# V1_0.net
KiCad netlist of a schematic drawn in Altium Designer
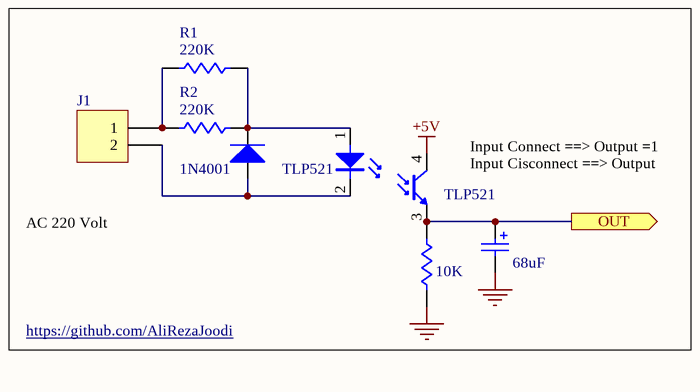
[diagram p0: V1.0.SchDoc]

(export (version "E")
  (design (tool "Eeschema 10.0.6"))
  (components
    (comp (ref "C1")
      (value "68uF")
      (footprint "Cap_D")
      (description "Polarized Capacitor (Radial)")
      (fields
        (field (name "MANUFACTURER") "Generic Components")
        (field (name "Comment") "CAP")
        (field (name "PUBLISHER") "Altium Limited")
      )
      (libsource (lib "Miscellaneous Devices") (part "Cap Pol1"))
    )
    (comp (ref "D1")
      (value "1N4001")
      (footprint "MELF-D3516-1406")
      (description "Default Diode")
      (fields
        (field (name "MANUFACTURER") "Generic Components")
        (field (name "Comment") "D1")
        (field (name "PUBLISHER") "Altium Limited")
      )
      (libsource (lib "Miscellaneous Devices") (part "Diode"))
    )
    (comp (ref "J1")
      (value "J9")
      (footprint "Fonics_2PIN_1")
      (description "Header, 2-Pin")
      (fields (field (name "PUBLISHER") "Altium Limited"))
      (libsource (lib "Miscellaneous Connectors") (part "Header 2"))
    )
    (comp (ref "R1")
      (value "220K")
      (footprint "0805")
      (description "Resistor")
      (fields
        (field (name "MANUFACTURER") "Generic Components")
        (field (name "Comment") "RES")
        (field (name "PUBLISHER") "Altium Limited")
      )
      (libsource (lib "Miscellaneous Devices") (part "Res1"))
    )
    (comp (ref "R2")
      (value "220K")
      (footprint "0805")
      (description "Resistor")
      (fields
        (field (name "MANUFACTURER") "Generic Components")
        (field (name "Comment") "RES")
        (field (name "PUBLISHER") "Altium Limited")
      )
      (libsource (lib "Miscellaneous Devices") (part "Res1"))
    )
    (comp (ref "R3")
      (value "10K")
      (footprint "0805")
      (description "Resistor")
      (fields
        (field (name "MANUFACTURER") "Generic Components")
        (field (name "Comment") "RES")
        (field (name "PUBLISHER") "Altium Limited")
      )
      (libsource (lib "Miscellaneous Devices") (part "Res1"))
    )
    (comp (ref "U1")
      (value "TLP521")
      (footprint "SMD_4PIN")
      (fields (field (name "PUBLISHER") "Altium Limited"))
      (libsource (lib "my Libraries") (part "Optoisolator"))
    )
  )
  (nets
    (net (code "1") (name "+5V") (class "Default")
      (node (ref "U1") (pin "4") (pinfunction "C_4") (pintype "passive"))
    )
    (net (code "2") (name "/OUT") (class "Default")
      (node (ref "C1") (pin "1") (pinfunction "1_1") (pintype "passive"))
      (node (ref "R3") (pin "1") (pinfunction "1_1") (pintype "passive"))
      (node (ref "U1") (pin "3") (pinfunction "E_3") (pintype "passive"))
    )
    (net (code "3") (name "GND") (class "Default")
      (node (ref "C1") (pin "2") (pinfunction "2_2") (pintype "passive"))
      (node (ref "R3") (pin "2") (pinfunction "2_2") (pintype "passive"))
    )
    (net (code "4") (name "Net-(D1-A)") (class "Default")
      (node (ref "D1") (pin "1") (pinfunction "A_1") (pintype "passive"))
      (node (ref "J1") (pin "2") (pinfunction "2_2") (pintype "passive"))
      (node (ref "U1") (pin "2") (pinfunction "K_2") (pintype "power_in"))
    )
    (net (code "5") (name "Net-(D1-K)") (class "Default")
      (node (ref "D1") (pin "2") (pinfunction "K_2") (pintype "passive"))
      (node (ref "R1") (pin "2") (pinfunction "2_2") (pintype "passive"))
      (node (ref "R2") (pin "2") (pinfunction "2_2") (pintype "passive"))
      (node (ref "U1") (pin "1") (pinfunction "A_1") (pintype "power_in"))
    )
    (net (code "6") (name "Net-(J1-Pad1)") (class "Default")
      (node (ref "J1") (pin "1") (pinfunction "1_1") (pintype "passive"))
      (node (ref "R1") (pin "1") (pinfunction "1_1") (pintype "passive"))
      (node (ref "R2") (pin "1") (pinfunction "1_1") (pintype "passive"))
    )
  )
)
